# RT.net
KiCad netlist of a schematic drawn in Altium Designer
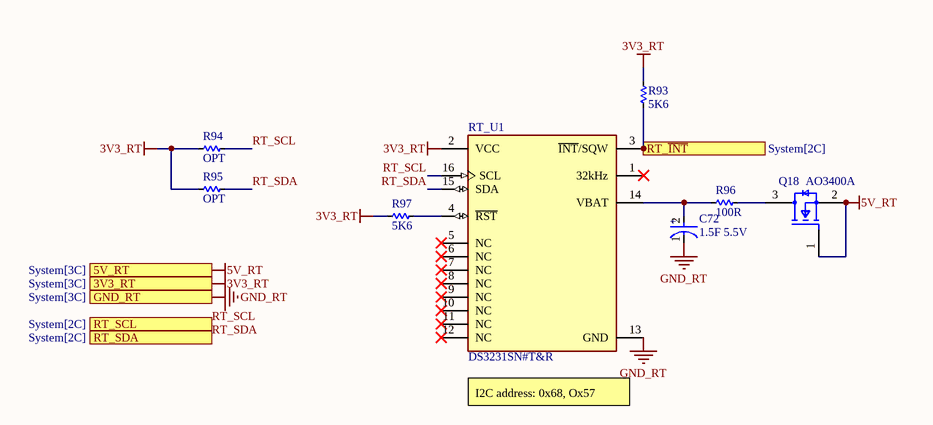
[diagram p0: RT.SchDoc]

(export (version "E")
  (design (tool "Eeschema 10.0.6"))
  (components
    (comp (ref "C72")
      (value "1.5F 5.5V")
      (footprint "FP-FT0H474ZF-MFG")
      (description "Siêu tụ 1.5F 5.5V chân nằm SE-5R5-D155VYC3H")
      (fields
        (field (name "OCTOPART") "https://octopart.com/ft0h474zf-kemet-30531665")
        (field (name "MANUFACTURER") "KEMET")
      )
      (libsource (lib "Altium Content Vault") (part "203bc49f2ac43e59fd269a8c329ed05"))
    )
    (comp (ref "Q18")
      (value "AO3400A")
      (footprint "FP-SOT23-IPC_A")
      (description "OPT")
      (libsource (lib "Altium Content Vault") (part "0a9ea7c96deaaede766a5b531c28de0"))
    )
    (comp (ref "R93")
      (value "5K6")
      (footprint "RES-SMD-0603")
      (description "Resistor 0603")
      (fields
        (field (name "MANUFACTURER") "Generic Components")
        (field (name "PUBLISHER") "Altium Hobart Technology Centre")
      )
      (libsource (lib "TechMT.VN_Lib_Project v2") (part "Res-SMD"))
    )
    (comp (ref "R94")
      (value "OPT")
      (footprint "RES-SMD-0603")
      (description "Resistor 0603")
      (fields
        (field (name "MANUFACTURER") "Generic Components")
        (field (name "PUBLISHER") "Altium Hobart Technology Centre")
      )
      (libsource (lib "TechMT.VN_Lib_Project v2") (part "Res-SMD"))
    )
    (comp (ref "R95")
      (value "OPT")
      (footprint "RES-SMD-0603")
      (description "Resistor 0603")
      (fields
        (field (name "MANUFACTURER") "Generic Components")
        (field (name "PUBLISHER") "Altium Hobart Technology Centre")
      )
      (libsource (lib "TechMT.VN_Lib_Project v2") (part "Res-SMD"))
    )
    (comp (ref "R96")
      (value "100R")
      (footprint "RES-SMD-0805")
      (description "Res 0805")
      (fields
        (field (name "MANUFACTURER") "Generic Components")
        (field (name "PUBLISHER") "Altium Hobart Technology Centre")
      )
      (libsource (lib "TechMT.VN_Lib_Project v2") (part "Res-SMD"))
    )
    (comp (ref "R97")
      (value "5K6")
      (footprint "RES-SMD-0603")
      (description "Resistor 0603")
      (fields
        (field (name "MANUFACTURER") "Generic Components")
        (field (name "PUBLISHER") "Altium Hobart Technology Centre")
      )
      (libsource (lib "TechMT.VN_Lib_Project v2") (part "Res-SMD"))
    )
    (comp (ref "RT_U1")
      (value "DS3231SN#T&R")
      (footprint "FP-W16-H2-MFG")
      (description "IC RTC CLK/CALENDAR I2C 16-SOIC")
      (libsource (lib "Altium Content Vault") (part "49e129a02c1e013a88f81c98964c20e"))
    )
  )
  (nets
    (net (code "1") (name "/RT_SCL") (class "Default")
      (node (ref "R94") (pin "1") (pinfunction "1_1") (pintype "passive"))
      (node (ref "RT_U1") (pin "16") (pinfunction "SCL_16") (pintype "input"))
    )
    (net (code "2") (name "/RT_SDA") (class "Default")
      (node (ref "R95") (pin "1") (pinfunction "1_1") (pintype "passive"))
      (node (ref "RT_U1") (pin "15") (pinfunction "SDA_15") (pintype "bidirectional"))
    )
    (net (code "3") (name "/RT_~{INT}") (class "Default")
      (node (ref "R93") (pin "1") (pinfunction "1_1") (pintype "passive"))
      (node (ref "RT_U1") (pin "3") (pinfunction "~{INT}/SQW_3") (pintype "open_collector"))
    )
    (net (code "4") (name "3V3_RT") (class "Default")
      (node (ref "R93") (pin "2") (pinfunction "2_2") (pintype "passive"))
      (node (ref "R94") (pin "2") (pinfunction "2_2") (pintype "passive"))
      (node (ref "R95") (pin "2") (pinfunction "2_2") (pintype "passive"))
      (node (ref "R97") (pin "2") (pinfunction "2_2") (pintype "passive"))
      (node (ref "RT_U1") (pin "2") (pinfunction "VCC_2") (pintype "power_in"))
    )
    (net (code "5") (name "5V_RT") (class "Default")
      (node (ref "Q18") (pin "1") (pinfunction "G_1") (pintype "passive"))
      (node (ref "Q18") (pin "2") (pinfunction "S_2") (pintype "passive"))
    )
    (net (code "6") (name "GND_RT") (class "Default")
      (node (ref "C72") (pin "1") (pinfunction "C_1") (pintype "passive"))
      (node (ref "RT_U1") (pin "13") (pinfunction "GND_13") (pintype "power_in"))
    )
    (net (code "7") (name "Net-(C72-A)") (class "Default")
      (node (ref "C72") (pin "2") (pinfunction "A_2") (pintype "passive"))
      (node (ref "R96") (pin "1") (pinfunction "1_1") (pintype "passive"))
      (node (ref "RT_U1") (pin "14") (pinfunction "VBAT_14") (pintype "power_in"))
    )
    (net (code "8") (name "Net-(Q18-D)") (class "Default")
      (node (ref "Q18") (pin "3") (pinfunction "D_3") (pintype "passive"))
      (node (ref "R96") (pin "2") (pinfunction "2_2") (pintype "passive"))
    )
    (net (code "9") (name "Net-(RT_U1-~{RST})") (class "Default")
      (node (ref "R97") (pin "1") (pinfunction "1_1") (pintype "passive"))
      (node (ref "RT_U1") (pin "4") (pinfunction "~{RST}_4") (pintype "bidirectional"))
    )
    (net (code "10") (name "unconnected-(RT_U1-32kHz-Pad1)") (class "Default")
      (node (ref "RT_U1") (pin "1") (pinfunction "32kHz_1") (pintype "open_collector+no_connect"))
    )
    (net (code "11") (name "unconnected-(RT_U1-NC-Pad5)") (class "Default")
      (node (ref "RT_U1") (pin "5") (pinfunction "NC_5") (pintype "passive+no_connect"))
    )
    (net (code "12") (name "unconnected-(RT_U1-NC-Pad6)") (class "Default")
      (node (ref "RT_U1") (pin "6") (pinfunction "NC_6") (pintype "passive+no_connect"))
    )
    (net (code "13") (name "unconnected-(RT_U1-NC-Pad7)") (class "Default")
      (node (ref "RT_U1") (pin "7") (pinfunction "NC_7") (pintype "passive+no_connect"))
    )
    (net (code "14") (name "unconnected-(RT_U1-NC-Pad8)") (class "Default")
      (node (ref "RT_U1") (pin "8") (pinfunction "NC_8") (pintype "passive+no_connect"))
    )
    (net (code "15") (name "unconnected-(RT_U1-NC-Pad9)") (class "Default")
      (node (ref "RT_U1") (pin "9") (pinfunction "NC_9") (pintype "passive+no_connect"))
    )
    (net (code "16") (name "unconnected-(RT_U1-NC-Pad10)") (class "Default")
      (node (ref "RT_U1") (pin "10") (pinfunction "NC_10") (pintype "passive+no_connect"))
    )
    (net (code "17") (name "unconnected-(RT_U1-NC-Pad11)") (class "Default")
      (node (ref "RT_U1") (pin "11") (pinfunction "NC_11") (pintype "passive+no_connect"))
    )
    (net (code "18") (name "unconnected-(RT_U1-NC-Pad12)") (class "Default")
      (node (ref "RT_U1") (pin "12") (pinfunction "NC_12") (pintype "passive+no_connect"))
    )
  )
)
